# Priemnic.net
KiCad netlist of a schematic drawn in Altium Designer
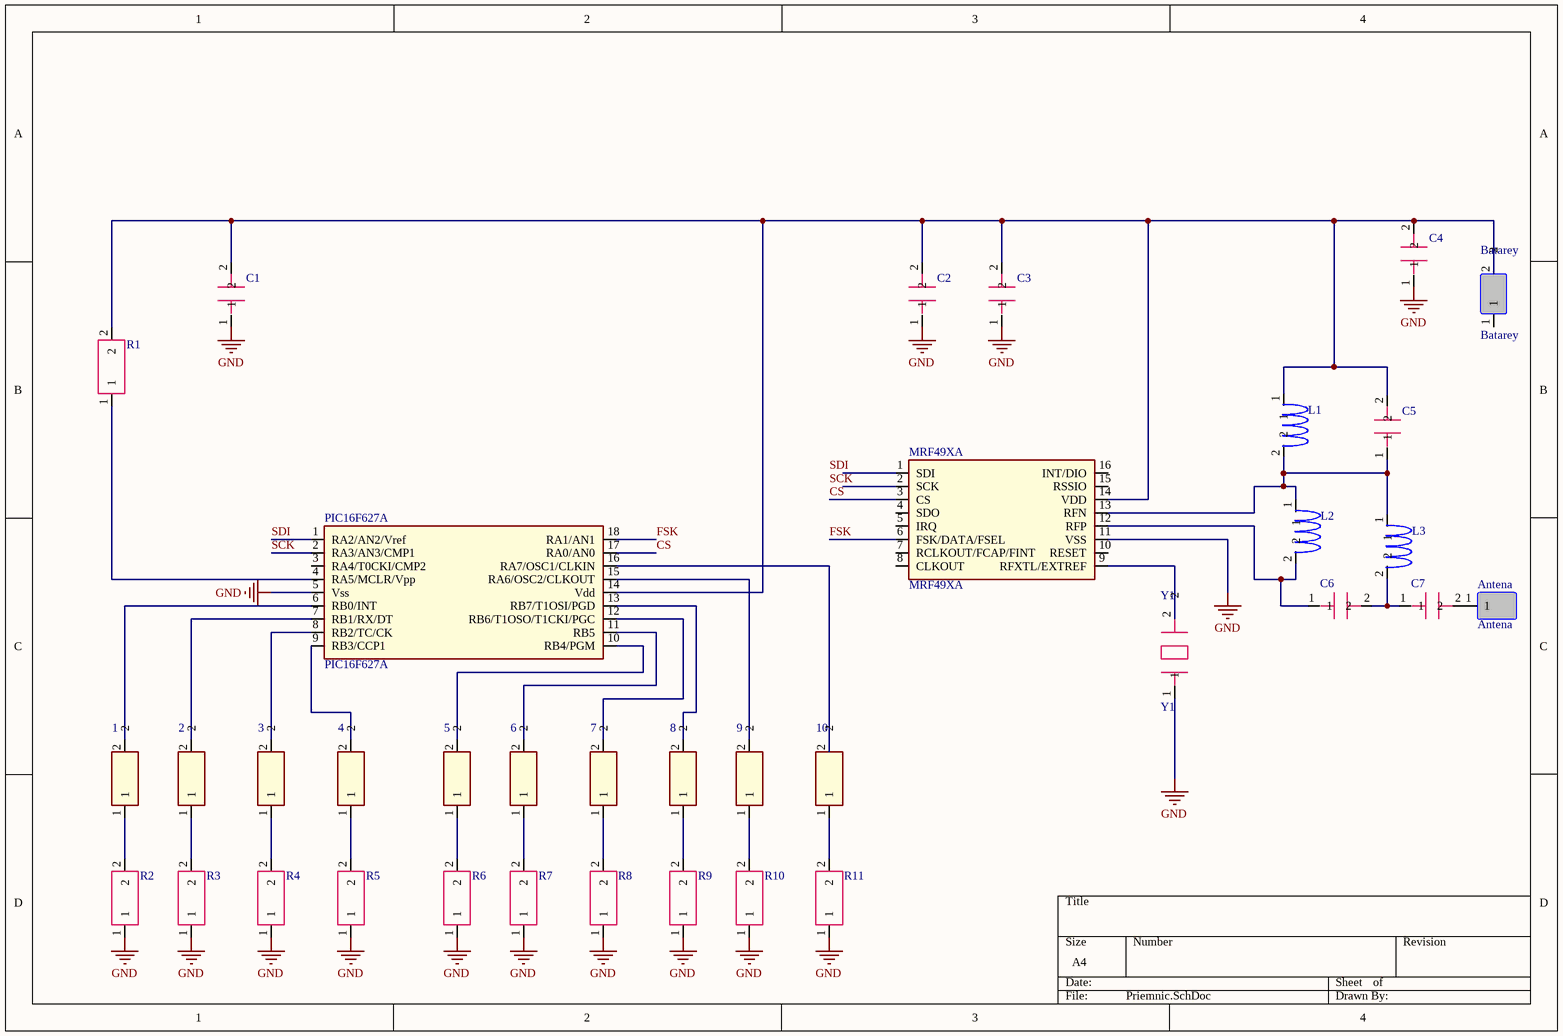
[diagram p0: Priemnic.SchDoc]

(export (version "E")
  (design (tool "Eeschema 10.0.6"))
  (components
    (comp (ref "1")
      (value "~")
      (footprint "RCU:Light-emitting diode")
      (libsource (lib "RCU") (part "Light-emitting diode"))
    )
    (comp (ref "2")
      (value "~")
      (footprint "RCU:Light-emitting diode")
      (libsource (lib "RCU") (part "Light-emitting diode"))
    )
    (comp (ref "3")
      (value "~")
      (footprint "RCU:Light-emitting diode")
      (libsource (lib "RCU") (part "Light-emitting diode"))
    )
    (comp (ref "4")
      (value "~")
      (footprint "RCU:Light-emitting diode")
      (libsource (lib "RCU") (part "Light-emitting diode"))
    )
    (comp (ref "5")
      (value "~")
      (footprint "RCU:Light-emitting diode")
      (libsource (lib "RCU") (part "Light-emitting diode"))
    )
    (comp (ref "6")
      (value "~")
      (footprint "RCU:Light-emitting diode")
      (libsource (lib "RCU") (part "Light-emitting diode"))
    )
    (comp (ref "7")
      (value "~")
      (footprint "RCU:Light-emitting diode")
      (libsource (lib "RCU") (part "Light-emitting diode"))
    )
    (comp (ref "8")
      (value "~")
      (footprint "RCU:Light-emitting diode")
      (libsource (lib "RCU") (part "Light-emitting diode"))
    )
    (comp (ref "9")
      (value "~")
      (footprint "RCU:Light-emitting diode")
      (libsource (lib "RCU") (part "Light-emitting diode"))
    )
    (comp (ref "10")
      (value "~")
      (footprint "RCU:Light-emitting diode")
      (libsource (lib "RCU") (part "Light-emitting diode"))
    )
    (comp (ref "Antena") (value "Antena") (footprint "RCU:Anteny") (libsource (lib "RCU") (part "Antena")))
    (comp (ref "Batarey")
      (value "Batarey")
      (footprint "RCU:Batarey")
      (libsource (lib "RCU") (part "Batarey"))
    )
    (comp (ref "C1") (value "~") (footprint "RCU:С0805") (libsource (lib "RCU") (part "Capacity")))
    (comp (ref "C2") (value "~") (footprint "RCU:С0805") (libsource (lib "RCU") (part "Capacity")))
    (comp (ref "C3") (value "~") (footprint "RCU:С0805") (libsource (lib "RCU") (part "Capacity")))
    (comp (ref "C4") (value "~") (footprint "RCU:С0805") (libsource (lib "RCU") (part "Capacity")))
    (comp (ref "C5") (value "~") (footprint "RCU:С0805") (libsource (lib "RCU") (part "Capacity")))
    (comp (ref "C6") (value "~") (footprint "RCU:С0805") (libsource (lib "RCU") (part "Capacity")))
    (comp (ref "C7") (value "~") (footprint "RCU:С0805") (libsource (lib "RCU") (part "Capacity")))
    (comp (ref "L1") (value "~") (footprint "RCU:L?") (libsource (lib "RCU") (part "Inductance")))
    (comp (ref "L2") (value "~") (footprint "RCU:L?") (libsource (lib "RCU") (part "Inductance")))
    (comp (ref "L3") (value "~") (footprint "RCU:L?") (libsource (lib "RCU") (part "Inductance")))
    (comp (ref "MRF49XA")
      (value "MRF49XA")
      (footprint "RCU:MRF49XA")
      (libsource (lib "RCU") (part "MRF49XA"))
    )
    (comp (ref "PIC16F627A")
      (value "PIC16F627A")
      (footprint "RCU:PIC16F627A")
      (libsource (lib "RCU") (part "PIC16F627A"))
    )
    (comp (ref "R1") (value "~") (footprint "RCU:R0805") (libsource (lib "RCU") (part "Rezistor")))
    (comp (ref "R2") (value "~") (footprint "RCU:R0805") (libsource (lib "RCU") (part "Rezistor")))
    (comp (ref "R3") (value "~") (footprint "RCU:R0805") (libsource (lib "RCU") (part "Rezistor")))
    (comp (ref "R4") (value "~") (footprint "RCU:R0805") (libsource (lib "RCU") (part "Rezistor")))
    (comp (ref "R5") (value "~") (footprint "RCU:R0805") (libsource (lib "RCU") (part "Rezistor")))
    (comp (ref "R6") (value "~") (footprint "RCU:R0805") (libsource (lib "RCU") (part "Rezistor")))
    (comp (ref "R7") (value "~") (footprint "RCU:R0805") (libsource (lib "RCU") (part "Rezistor")))
    (comp (ref "R8") (value "~") (footprint "RCU:R0805") (libsource (lib "RCU") (part "Rezistor")))
    (comp (ref "R9") (value "~") (footprint "RCU:R0805") (libsource (lib "RCU") (part "Rezistor")))
    (comp (ref "R10") (value "~") (footprint "RCU:R0805") (libsource (lib "RCU") (part "Rezistor")))
    (comp (ref "R11") (value "~") (footprint "RCU:R0805") (libsource (lib "RCU") (part "Rezistor")))
    (comp (ref "Y1") (value "Y1") (footprint "RCU:Quartz") (libsource (lib "RCU") (part "Quartz")))
  )
  (nets
    (net (code "1") (name "/CS") (class "Default")
      (node (ref "MRF49XA") (pin "3") (pinfunction "CS_3") (pintype "passive"))
      (node (ref "PIC16F627A") (pin "17") (pinfunction "RA0/AN0_17") (pintype "passive"))
    )
    (net (code "2") (name "/FSK") (class "Default")
      (node (ref "MRF49XA") (pin "6") (pinfunction "FSK/DATA/FSEL_6") (pintype "passive"))
      (node (ref "PIC16F627A") (pin "18") (pinfunction "RA1/AN1_18") (pintype "passive"))
    )
    (net (code "3") (name "/SCK") (class "Default")
      (node (ref "PIC16F627A") (pin "2") (pinfunction "RA3/AN3/CMP1_2") (pintype "passive"))
    )
    (net (code "4") (name "/SDI") (class "Default")
      (node (ref "PIC16F627A") (pin "1") (pinfunction "RA2/AN2/Vref_1") (pintype "passive"))
    )
    (net (code "5") (name "GND") (class "Default")
      (node (ref "C1") (pin "1") (pinfunction "1_1") (pintype "passive"))
      (node (ref "C2") (pin "1") (pinfunction "1_1") (pintype "passive"))
      (node (ref "C3") (pin "1") (pinfunction "1_1") (pintype "passive"))
      (node (ref "C4") (pin "1") (pinfunction "1_1") (pintype "passive"))
      (node (ref "MRF49XA") (pin "11") (pinfunction "VSS_11") (pintype "passive"))
      (node (ref "PIC16F627A") (pin "5") (pinfunction "Vss_5") (pintype "passive"))
      (node (ref "R10") (pin "1") (pinfunction "1_1") (pintype "passive"))
      (node (ref "R11") (pin "1") (pinfunction "1_1") (pintype "passive"))
      (node (ref "R2") (pin "1") (pinfunction "1_1") (pintype "passive"))
      (node (ref "R3") (pin "1") (pinfunction "1_1") (pintype "passive"))
      (node (ref "R4") (pin "1") (pinfunction "1_1") (pintype "passive"))
      (node (ref "R5") (pin "1") (pinfunction "1_1") (pintype "passive"))
      (node (ref "R6") (pin "1") (pinfunction "1_1") (pintype "passive"))
      (node (ref "R7") (pin "1") (pinfunction "1_1") (pintype "passive"))
      (node (ref "R8") (pin "1") (pinfunction "1_1") (pintype "passive"))
      (node (ref "R9") (pin "1") (pinfunction "1_1") (pintype "passive"))
      (node (ref "Y1") (pin "1") (pinfunction "1_1") (pintype "passive"))
    )
    (net (code "6") (name "Net-(1-Pad1)") (class "Default")
      (node (ref "1") (pin "1") (pinfunction "1_1") (pintype "passive"))
      (node (ref "R2") (pin "2") (pinfunction "2_2") (pintype "passive"))
    )
    (net (code "7") (name "Net-(2-Pad1)") (class "Default")
      (node (ref "2") (pin "1") (pinfunction "1_1") (pintype "passive"))
      (node (ref "R3") (pin "2") (pinfunction "2_2") (pintype "passive"))
    )
    (net (code "8") (name "Net-(3-Pad1)") (class "Default")
      (node (ref "3") (pin "1") (pinfunction "1_1") (pintype "passive"))
      (node (ref "R4") (pin "2") (pinfunction "2_2") (pintype "passive"))
    )
    (net (code "9") (name "Net-(4-Pad1)") (class "Default")
      (node (ref "4") (pin "1") (pinfunction "1_1") (pintype "passive"))
      (node (ref "R5") (pin "2") (pinfunction "2_2") (pintype "passive"))
    )
    (net (code "10") (name "Net-(5-Pad1)") (class "Default")
      (node (ref "5") (pin "1") (pinfunction "1_1") (pintype "passive"))
      (node (ref "R6") (pin "2") (pinfunction "2_2") (pintype "passive"))
    )
    (net (code "11") (name "Net-(6-Pad1)") (class "Default")
      (node (ref "6") (pin "1") (pinfunction "1_1") (pintype "passive"))
      (node (ref "R7") (pin "2") (pinfunction "2_2") (pintype "passive"))
    )
    (net (code "12") (name "Net-(7-Pad1)") (class "Default")
      (node (ref "7") (pin "1") (pinfunction "1_1") (pintype "passive"))
      (node (ref "R8") (pin "2") (pinfunction "2_2") (pintype "passive"))
    )
    (net (code "13") (name "Net-(8-Pad1)") (class "Default")
      (node (ref "8") (pin "1") (pinfunction "1_1") (pintype "passive"))
      (node (ref "R9") (pin "2") (pinfunction "2_2") (pintype "passive"))
    )
    (net (code "14") (name "Net-(9-Pad1)") (class "Default")
      (node (ref "9") (pin "1") (pinfunction "1_1") (pintype "passive"))
      (node (ref "R10") (pin "2") (pinfunction "2_2") (pintype "passive"))
    )
    (net (code "15") (name "Net-(10-Pad1)") (class "Default")
      (node (ref "10") (pin "1") (pinfunction "1_1") (pintype "passive"))
      (node (ref "R11") (pin "2") (pinfunction "2_2") (pintype "passive"))
    )
    (net (code "16") (name "Net-(Antena-Pad1)") (class "Default")
      (node (ref "Antena") (pin "1") (pinfunction "1_1") (pintype "passive"))
      (node (ref "C7") (pin "2") (pinfunction "2_2") (pintype "passive"))
    )
    (net (code "17") (name "Net-(C6-Pad2)") (class "Default")
      (node (ref "C6") (pin "2") (pinfunction "2_2") (pintype "passive"))
      (node (ref "C7") (pin "1") (pinfunction "1_1") (pintype "passive"))
      (node (ref "L3") (pin "2") (pinfunction "2_2") (pintype "passive"))
    )
    (net (code "18") (name "Net-(MRF49XA-RFN)") (class "Default")
      (node (ref "C5") (pin "1") (pinfunction "1_1") (pintype "passive"))
      (node (ref "L1") (pin "2") (pinfunction "2_2") (pintype "passive"))
      (node (ref "L2") (pin "1") (pinfunction "1_1") (pintype "passive"))
      (node (ref "L3") (pin "1") (pinfunction "1_1") (pintype "passive"))
      (node (ref "MRF49XA") (pin "13") (pinfunction "RFN_13") (pintype "passive"))
    )
    (net (code "19") (name "Net-(MRF49XA-RFP)") (class "Default")
      (node (ref "C6") (pin "1") (pinfunction "1_1") (pintype "passive"))
      (node (ref "L2") (pin "2") (pinfunction "2_2") (pintype "passive"))
      (node (ref "MRF49XA") (pin "12") (pinfunction "RFP_12") (pintype "passive"))
    )
    (net (code "20") (name "Net-(MRF49XA-RFXTL{slash}EXTREF)") (class "Default")
      (node (ref "MRF49XA") (pin "9") (pinfunction "RFXTL/EXTREF_9") (pintype "passive"))
      (node (ref "Y1") (pin "2") (pinfunction "2_2") (pintype "passive"))
    )
    (net (code "21") (name "Net-(MRF49XA-VDD)") (class "Default")
      (node (ref "Batarey") (pin "2") (pinfunction "2_2") (pintype "passive"))
      (node (ref "C1") (pin "2") (pinfunction "2_2") (pintype "passive"))
      (node (ref "C2") (pin "2") (pinfunction "2_2") (pintype "passive"))
      (node (ref "C3") (pin "2") (pinfunction "2_2") (pintype "passive"))
      (node (ref "C4") (pin "2") (pinfunction "2_2") (pintype "passive"))
      (node (ref "C5") (pin "2") (pinfunction "2_2") (pintype "passive"))
      (node (ref "L1") (pin "1") (pinfunction "1_1") (pintype "passive"))
      (node (ref "MRF49XA") (pin "14") (pinfunction "VDD_14") (pintype "passive"))
      (node (ref "PIC16F627A") (pin "14") (pinfunction "Vdd_14") (pintype "passive"))
      (node (ref "R1") (pin "2") (pinfunction "2_2") (pintype "passive"))
    )
    (net (code "22") (name "Net-(PIC16F627A-RA5{slash}MCLR{slash}Vpp)") (class "Default")
      (node (ref "PIC16F627A") (pin "4") (pinfunction "RA5/MCLR/Vpp_4") (pintype "passive"))
      (node (ref "R1") (pin "1") (pinfunction "1_1") (pintype "passive"))
    )
    (net (code "23") (name "Net-(PIC16F627A-RA7{slash}OSC1{slash}CLKIN)") (class "Default")
      (node (ref "10") (pin "2") (pinfunction "2_2") (pintype "passive"))
      (node (ref "PIC16F627A") (pin "16") (pinfunction "RA7/OSC1/CLKIN_16") (pintype "passive"))
    )
    (net (code "24") (name "unconnected-(1-Pad2)") (class "Default")
      (node (ref "1") (pin "2") (pinfunction "2_2") (pintype "passive"))
    )
    (net (code "25") (name "unconnected-(2-Pad2)") (class "Default")
      (node (ref "2") (pin "2") (pinfunction "2_2") (pintype "passive"))
    )
    (net (code "26") (name "unconnected-(3-Pad2)") (class "Default")
      (node (ref "3") (pin "2") (pinfunction "2_2") (pintype "passive"))
    )
    (net (code "27") (name "unconnected-(4-Pad2)") (class "Default")
      (node (ref "4") (pin "2") (pinfunction "2_2") (pintype "passive"))
    )
    (net (code "28") (name "unconnected-(5-Pad2)") (class "Default")
      (node (ref "5") (pin "2") (pinfunction "2_2") (pintype "passive"))
    )
    (net (code "29") (name "unconnected-(6-Pad2)") (class "Default")
      (node (ref "6") (pin "2") (pinfunction "2_2") (pintype "passive"))
    )
    (net (code "30") (name "unconnected-(7-Pad2)") (class "Default")
      (node (ref "7") (pin "2") (pinfunction "2_2") (pintype "passive"))
    )
    (net (code "31") (name "unconnected-(8-Pad2)") (class "Default")
      (node (ref "8") (pin "2") (pinfunction "2_2") (pintype "passive"))
    )
    (net (code "32") (name "unconnected-(9-Pad2)") (class "Default")
      (node (ref "9") (pin "2") (pinfunction "2_2") (pintype "passive"))
    )
    (net (code "33") (name "unconnected-(Batarey-Pad1)") (class "Default")
      (node (ref "Batarey") (pin "1") (pinfunction "1_1") (pintype "passive"))
    )
    (net (code "34") (name "unconnected-(MRF49XA-CLKOUT-Pad8)") (class "Default")
      (node (ref "MRF49XA") (pin "8") (pinfunction "CLKOUT_8") (pintype "passive"))
    )
    (net (code "35") (name "unconnected-(MRF49XA-INT{slash}DIO-Pad16)") (class "Default")
      (node (ref "MRF49XA") (pin "16") (pinfunction "INT/DIO_16") (pintype "passive"))
    )
    (net (code "36") (name "unconnected-(MRF49XA-IRQ-Pad5)") (class "Default")
      (node (ref "MRF49XA") (pin "5") (pinfunction "IRQ_5") (pintype "passive"))
    )
    (net (code "37") (name "unconnected-(MRF49XA-RCLKOUT{slash}FCAP{slash}FINT-Pad7)") (class "Default")
      (node (ref "MRF49XA") (pin "7") (pinfunction "RCLKOUT/FCAP/FINT_7") (pintype "passive"))
    )
    (net (code "38") (name "unconnected-(MRF49XA-RESET-Pad10)") (class "Default")
      (node (ref "MRF49XA") (pin "10") (pinfunction "RESET_10") (pintype "passive"))
    )
    (net (code "39") (name "unconnected-(MRF49XA-RSSIO-Pad15)") (class "Default")
      (node (ref "MRF49XA") (pin "15") (pinfunction "RSSIO_15") (pintype "passive"))
    )
    (net (code "40") (name "unconnected-(MRF49XA-SCK-Pad2)") (class "Default")
      (node (ref "MRF49XA") (pin "2") (pinfunction "SCK_2") (pintype "passive"))
    )
    (net (code "41") (name "unconnected-(MRF49XA-SDI-Pad1)") (class "Default")
      (node (ref "MRF49XA") (pin "1") (pinfunction "SDI_1") (pintype "passive"))
    )
    (net (code "42") (name "unconnected-(MRF49XA-SDO-Pad4)") (class "Default")
      (node (ref "MRF49XA") (pin "4") (pinfunction "SDO_4") (pintype "passive"))
    )
    (net (code "43") (name "unconnected-(PIC16F627A-RA4{slash}T0CKI{slash}CMP2-Pad3)") (class "Default")
      (node (ref "PIC16F627A") (pin "3") (pinfunction "RA4/T0CKI/CMP2_3") (pintype "passive"))
    )
    (net (code "44") (name "unconnected-(PIC16F627A-RA6{slash}OSC2{slash}CLKOUT-Pad15)") (class "Default")
      (node (ref "PIC16F627A") (pin "15") (pinfunction "RA6/OSC2/CLKOUT_15") (pintype "passive"))
    )
    (net (code "45") (name "unconnected-(PIC16F627A-RB0{slash}INT-Pad6)") (class "Default")
      (node (ref "PIC16F627A") (pin "6") (pinfunction "RB0/INT_6") (pintype "passive"))
    )
    (net (code "46") (name "unconnected-(PIC16F627A-RB1{slash}RX{slash}DT-Pad7)") (class "Default")
      (node (ref "PIC16F627A") (pin "7") (pinfunction "RB1/RX/DT_7") (pintype "passive"))
    )
    (net (code "47") (name "unconnected-(PIC16F627A-RB2{slash}TC{slash}CK-Pad8)") (class "Default")
      (node (ref "PIC16F627A") (pin "8") (pinfunction "RB2/TC/CK_8") (pintype "passive"))
    )
    (net (code "48") (name "unconnected-(PIC16F627A-RB3{slash}CCP1-Pad9)") (class "Default")
      (node (ref "PIC16F627A") (pin "9") (pinfunction "RB3/CCP1_9") (pintype "passive"))
    )
    (net (code "49") (name "unconnected-(PIC16F627A-RB4{slash}PGM-Pad10)") (class "Default")
      (node (ref "PIC16F627A") (pin "10") (pinfunction "RB4/PGM_10") (pintype "passive"))
    )
    (net (code "50") (name "unconnected-(PIC16F627A-RB5-Pad11)") (class "Default")
      (node (ref "PIC16F627A") (pin "11") (pinfunction "RB5_11") (pintype "passive"))
    )
    (net (code "51") (name "unconnected-(PIC16F627A-RB6{slash}T1OSO{slash}T1CKI{slash}PGC-Pad12)") (class "Default")
      (node (ref "PIC16F627A") (pin "12") (pinfunction "RB6/T1OSO/T1CKI/PGC_12") (pintype "passive"))
    )
    (net (code "52") (name "unconnected-(PIC16F627A-RB7{slash}T1OSI{slash}PGD-Pad13)") (class "Default")
      (node (ref "PIC16F627A") (pin "13") (pinfunction "RB7/T1OSI/PGD_13") (pintype "passive"))
    )
  )
)
